# Sheet_STM32_Microcontroller.net
KiCad netlist of a schematic drawn in Altium Designer
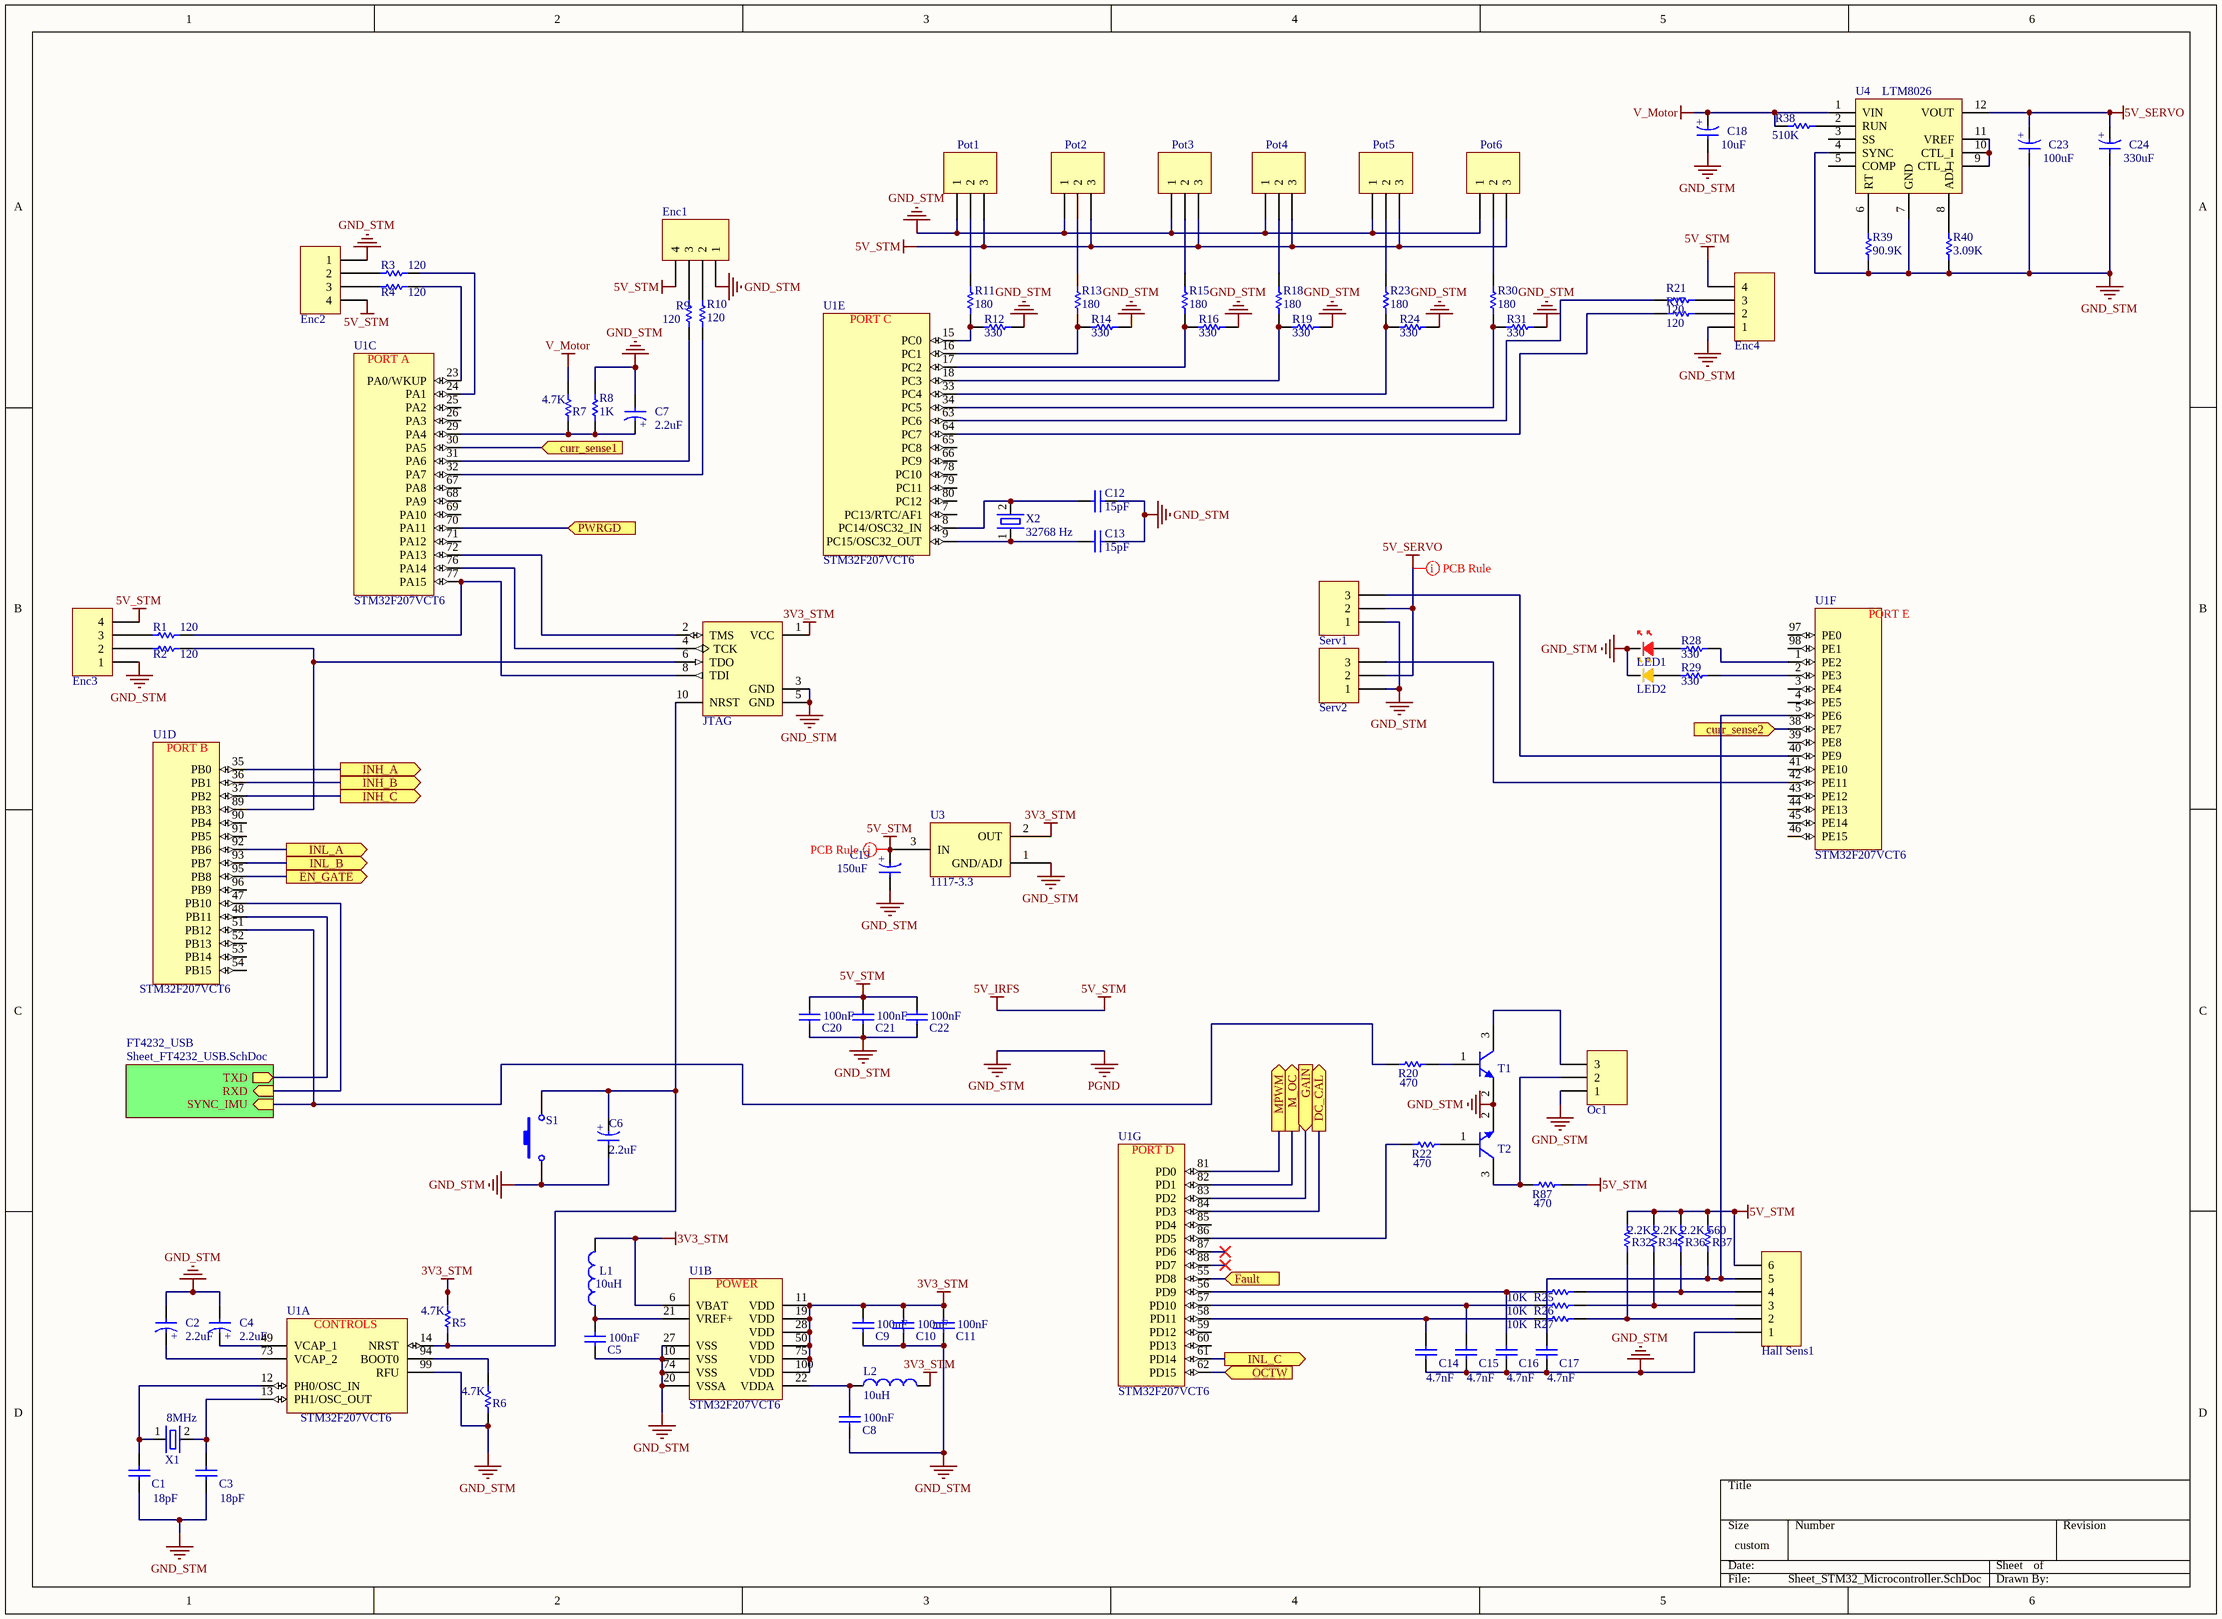
[diagram p0: Sheet_STM32_Microcontroller.SchDoc]

(export (version "E")
  (design (tool "Eeschema 10.0.6"))
  (components
    (comp (ref "C1")
      (value "18pF")
      (footprint "ARPG_PCB_LIB:1608[0603]")
      (description "Capacitor")
      (libsource (lib "AlmaLib1") (part "Cap_BP"))
    )
    (comp (ref "C2")
      (value "2.2uF")
      (footprint "ARPG_PCB_LIB:1608[0603] - Polar")
      (description "Capacitor")
      (libsource (lib "ARPG_PCB_LIB") (part "Cap_E"))
    )
    (comp (ref "C3")
      (value "18pF")
      (footprint "ARPG_PCB_LIB:1608[0603]")
      (description "Capacitor")
      (libsource (lib "AlmaLib1") (part "Cap_BP"))
    )
    (comp (ref "C4")
      (value "2.2uF")
      (footprint "ARPG_PCB_LIB:1608[0603] - Polar")
      (description "Capacitor")
      (libsource (lib "ARPG_PCB_LIB") (part "Cap_E"))
    )
    (comp (ref "C5")
      (value "100nF")
      (footprint "ARPG_PCB_LIB:1608[0603]")
      (description "Capacitor")
      (libsource (lib "AlmaLib1") (part "Cap_BP"))
    )
    (comp (ref "C6")
      (value "2.2uF")
      (footprint "ARPG_PCB_LIB:1608[0603] - Polar")
      (description "Capacitor")
      (libsource (lib "ARPG_PCB_LIB") (part "Cap_E"))
    )
    (comp (ref "C7")
      (value "2.2uF")
      (footprint "ARPG_PCB_LIB:1608[0603] - Polar")
      (description "Capacitor")
      (libsource (lib "ARPG_PCB_LIB") (part "Cap_E"))
    )
    (comp (ref "C8")
      (value "100nF")
      (footprint "ARPG_PCB_LIB:1608[0603]")
      (description "Capacitor")
      (libsource (lib "AlmaLib1") (part "Cap_BP"))
    )
    (comp (ref "C9")
      (value "100nF")
      (footprint "ARPG_PCB_LIB:1608[0603]")
      (description "Capacitor")
      (libsource (lib "AlmaLib1") (part "Cap_BP"))
    )
    (comp (ref "C10")
      (value "100nF")
      (footprint "ARPG_PCB_LIB:1608[0603]")
      (description "Capacitor")
      (libsource (lib "AlmaLib1") (part "Cap_BP"))
    )
    (comp (ref "C11")
      (value "100nF")
      (footprint "ARPG_PCB_LIB:1608[0603]")
      (description "Capacitor")
      (libsource (lib "AlmaLib1") (part "Cap_BP"))
    )
    (comp (ref "C12")
      (value "15pF")
      (footprint "ARPG_PCB_LIB:1608[0603]")
      (description "Capacitor")
      (libsource (lib "AlmaLib1") (part "Cap_BP"))
    )
    (comp (ref "C13")
      (value "15pF")
      (footprint "ARPG_PCB_LIB:1608[0603]")
      (description "Capacitor")
      (libsource (lib "AlmaLib1") (part "Cap_BP"))
    )
    (comp (ref "C14")
      (value "4.7nF")
      (footprint "ARPG_PCB_LIB:1608[0603]")
      (description "Capacitor")
      (libsource (lib "AlmaLib1") (part "Cap_BP"))
    )
    (comp (ref "C15")
      (value "4.7nF")
      (footprint "ARPG_PCB_LIB:1608[0603]")
      (description "Capacitor")
      (libsource (lib "AlmaLib1") (part "Cap_BP"))
    )
    (comp (ref "C16")
      (value "4.7nF")
      (footprint "ARPG_PCB_LIB:1608[0603]")
      (description "Capacitor")
      (libsource (lib "AlmaLib1") (part "Cap_BP"))
    )
    (comp (ref "C17")
      (value "4.7nF")
      (footprint "ARPG_PCB_LIB:1608[0603]")
      (description "Capacitor")
      (libsource (lib "AlmaLib1") (part "Cap_BP"))
    )
    (comp (ref "C18")
      (value "10uF")
      (footprint "ARPG_PCB_LIB:6032 [2312]")
      (description "Capacitor")
      (libsource (lib "AlmaLib1") (part "Cap_E"))
    )
    (comp (ref "C19")
      (value "150uF")
      (footprint "ARPG_PCB_LIB:6032 [2312]")
      (description "Capacitor")
      (libsource (lib "AlmaLib1") (part "Cap_E"))
    )
    (comp (ref "C20")
      (value "100nF")
      (footprint "ARPG_PCB_LIB:1608[0603]")
      (description "Capacitor")
      (libsource (lib "AlmaLib1") (part "Cap_BP"))
    )
    (comp (ref "C21")
      (value "100nF")
      (footprint "ARPG_PCB_LIB:1608[0603]")
      (description "Capacitor")
      (libsource (lib "AlmaLib1") (part "Cap_BP"))
    )
    (comp (ref "C22")
      (value "100nF")
      (footprint "ARPG_PCB_LIB:1608[0603]")
      (description "Capacitor")
      (libsource (lib "AlmaLib1") (part "Cap_BP"))
    )
    (comp (ref "C23")
      (value "100uF")
      (footprint "ARPG_PCB_LIB:6032 [2312]")
      (description "Capacitor")
      (libsource (lib "AlmaLib1") (part "Cap_E"))
    )
    (comp (ref "C24")
      (value "330uF")
      (footprint "ARPG_PCB_LIB:6032 [2312]")
      (description "Capacitor")
      (libsource (lib "AlmaLib1") (part "Cap_E"))
    )
    (comp (ref "H1")
      (value "Enc3")
      (footprint "ARPG_PCB_LIB:Header 4  -MolexPicoBlade")
      (libsource (lib "") (part "Header 4_1"))
    )
    (comp (ref "H2")
      (value "Enc2")
      (footprint "ARPG_PCB_LIB:Header 4  -MolexPicoBlade")
      (libsource (lib "AlmaLib1") (part "Header 4"))
    )
    (comp (ref "H3")
      (value "Enc1")
      (footprint "ARPG_PCB_LIB:Header 4  -MolexPicoBlade")
      (libsource (lib "") (part "Header 4_2"))
    )
    (comp (ref "H4")
      (value "JTAG")
      (footprint "ARPG_PCB_LIB:HDR-2*5-0.05_Without_Through_Hole")
      (description "USB JTAG Programmer")
      (libsource (lib "AlmaLib1") (part "JTAG-ARM"))
    )
    (comp (ref "H5")
      (value "Serv1")
      (footprint "HDR1X3")
      (description "Header, 3-Pin")
      (fields (field (name "PUBLISHER") "Altium Limited"))
      (libsource (lib "Miscellaneous Connectors") (part "Header 3"))
    )
    (comp (ref "H7")
      (value "Pot1")
      (footprint "ARPG_PCB_LIB:Header 3  -MolexPicoBlade")
      (libsource (lib "AlmaLib1") (part "Header 3"))
    )
    (comp (ref "H8")
      (value "Pot2")
      (footprint "ARPG_PCB_LIB:Header 3  -MolexPicoBlade")
      (libsource (lib "AlmaLib1") (part "Header 3"))
    )
    (comp (ref "H9")
      (value "Pot3")
      (footprint "ARPG_PCB_LIB:Header 3  -MolexPicoBlade")
      (libsource (lib "AlmaLib1") (part "Header 3"))
    )
    (comp (ref "H10")
      (value "Pot4")
      (footprint "ARPG_PCB_LIB:Header 3  -MolexPicoBlade")
      (libsource (lib "AlmaLib1") (part "Header 3"))
    )
    (comp (ref "H11")
      (value "Enc4")
      (footprint "ARPG_PCB_LIB:Header 4  -MolexPicoBlade")
      (libsource (lib "") (part "Header 4_3"))
    )
    (comp (ref "H12")
      (value "Pot5")
      (footprint "ARPG_PCB_LIB:Header 3  -MolexPicoBlade")
      (libsource (lib "AlmaLib1") (part "Header 3"))
    )
    (comp (ref "H13")
      (value "Serv2")
      (footprint "HDR1X3")
      (description "Header, 3-Pin")
      (fields (field (name "PUBLISHER") "Altium Limited"))
      (libsource (lib "Miscellaneous Connectors") (part "Header 3"))
    )
    (comp (ref "H16")
      (value "Pot6")
      (footprint "ARPG_PCB_LIB:Header 3  -MolexPicoBlade")
      (libsource (lib "AlmaLib1") (part "Header 3"))
    )
    (comp (ref "H17")
      (value "Oc1")
      (footprint "ARPG_PCB_LIB:Header 3  -MolexPicoBlade")
      (libsource (lib "AlmaLib1") (part "Header 3"))
    )
    (comp (ref "H18")
      (value "Hall Sens1")
      (footprint "ARPG_PCB_LIB:Header 6  ZH-SM4")
      (libsource (lib "AlmaLib1") (part "Header 6"))
    )
    (comp (ref "L1")
      (value "10uH")
      (footprint "ARPG_PCB_LIB:0805")
      (description "Inductor")
      (libsource (lib "AlmaLib1") (part "Inductor"))
    )
    (comp (ref "L2")
      (value "10uH")
      (footprint "ARPG_PCB_LIB:0805")
      (description "Inductor")
      (libsource (lib "AlmaLib1") (part "Inductor"))
    )
    (comp (ref "LED1")
      (value "LEDR")
      (footprint "ARPG_PCB_LIB:2012[0805]")
      (description "LED")
      (libsource (lib "AlmaLib1") (part "LED_R"))
    )
    (comp (ref "LED2")
      (value "LEDY")
      (footprint "ARPG_PCB_LIB:2012[0805]")
      (description "LED")
      (libsource (lib "AlmaLib1") (part "LED_Y"))
    )
    (comp (ref "R1")
      (value "120")
      (footprint "ARPG_PCB_LIB:1608[0603]")
      (description "Res")
      (libsource (lib "AlmaLib1") (part "Res"))
    )
    (comp (ref "R2")
      (value "120")
      (footprint "ARPG_PCB_LIB:1608[0603]")
      (description "Res")
      (libsource (lib "AlmaLib1") (part "Res"))
    )
    (comp (ref "R3")
      (value "120")
      (footprint "ARPG_PCB_LIB:1608[0603]")
      (description "Res")
      (libsource (lib "AlmaLib1") (part "Res"))
    )
    (comp (ref "R4")
      (value "120")
      (footprint "ARPG_PCB_LIB:1608[0603]")
      (description "Res")
      (libsource (lib "AlmaLib1") (part "Res"))
    )
    (comp (ref "R5")
      (value "4.7K")
      (footprint "ARPG_PCB_LIB:1608[0603]")
      (description "Res")
      (libsource (lib "AlmaLib1") (part "Res"))
    )
    (comp (ref "R6")
      (value "4.7K")
      (footprint "ARPG_PCB_LIB:1608[0603]")
      (description "Res")
      (libsource (lib "AlmaLib1") (part "Res"))
    )
    (comp (ref "R7")
      (value "4.7K")
      (footprint "ARPG_PCB_LIB:1608[0603]")
      (description "Res")
      (libsource (lib "AlmaLib1") (part "Res"))
    )
    (comp (ref "R8")
      (value "1K")
      (footprint "ARPG_PCB_LIB:1608[0603]")
      (description "Res")
      (libsource (lib "AlmaLib1") (part "Res"))
    )
    (comp (ref "R9")
      (value "120")
      (footprint "ARPG_PCB_LIB:1608[0603]")
      (description "Res")
      (libsource (lib "AlmaLib1") (part "Res"))
    )
    (comp (ref "R10")
      (value "120")
      (footprint "ARPG_PCB_LIB:1608[0603]")
      (description "Res")
      (libsource (lib "AlmaLib1") (part "Res"))
    )
    (comp (ref "R11")
      (value "180")
      (footprint "ARPG_PCB_LIB:1608[0603]")
      (description "Res")
      (libsource (lib "AlmaLib1") (part "Res"))
    )
    (comp (ref "R12")
      (value "330")
      (footprint "ARPG_PCB_LIB:1608[0603]")
      (description "Res")
      (libsource (lib "AlmaLib1") (part "Res"))
    )
    (comp (ref "R13")
      (value "180")
      (footprint "ARPG_PCB_LIB:1608[0603]")
      (description "Res")
      (libsource (lib "AlmaLib1") (part "Res"))
    )
    (comp (ref "R14")
      (value "330")
      (footprint "ARPG_PCB_LIB:1608[0603]")
      (description "Res")
      (libsource (lib "AlmaLib1") (part "Res"))
    )
    (comp (ref "R15")
      (value "180")
      (footprint "ARPG_PCB_LIB:1608[0603]")
      (description "Res")
      (libsource (lib "AlmaLib1") (part "Res"))
    )
    (comp (ref "R16")
      (value "330")
      (footprint "ARPG_PCB_LIB:1608[0603]")
      (description "Res")
      (libsource (lib "AlmaLib1") (part "Res"))
    )
    (comp (ref "R17")
      (value "120")
      (footprint "ARPG_PCB_LIB:1608[0603]")
      (description "Res")
      (libsource (lib "AlmaLib1") (part "Res"))
    )
    (comp (ref "R18")
      (value "180")
      (footprint "ARPG_PCB_LIB:1608[0603]")
      (description "Res")
      (libsource (lib "AlmaLib1") (part "Res"))
    )
    (comp (ref "R19")
      (value "330")
      (footprint "ARPG_PCB_LIB:1608[0603]")
      (description "Res")
      (libsource (lib "AlmaLib1") (part "Res"))
    )
    (comp (ref "R20")
      (value "470")
      (footprint "ARPG_PCB_LIB:1608[0603]")
      (description "Res")
      (libsource (lib "SchLib1") (part "Res"))
    )
    (comp (ref "R21")
      (value "120")
      (footprint "ARPG_PCB_LIB:1608[0603]")
      (description "Res")
      (libsource (lib "AlmaLib1") (part "Res"))
    )
    (comp (ref "R22")
      (value "470")
      (footprint "ARPG_PCB_LIB:1608[0603]")
      (description "Res")
      (libsource (lib "SchLib1") (part "Res"))
    )
    (comp (ref "R23")
      (value "180")
      (footprint "ARPG_PCB_LIB:1608[0603]")
      (description "Res")
      (libsource (lib "AlmaLib1") (part "Res"))
    )
    (comp (ref "R24")
      (value "330")
      (footprint "ARPG_PCB_LIB:1608[0603]")
      (description "Res")
      (libsource (lib "AlmaLib1") (part "Res"))
    )
    (comp (ref "R25")
      (value "10K")
      (footprint "ARPG_PCB_LIB:1608[0603]")
      (description "Res")
      (libsource (lib "AlmaLib1") (part "Res"))
    )
    (comp (ref "R26")
      (value "10K")
      (footprint "ARPG_PCB_LIB:1608[0603]")
      (description "Res")
      (libsource (lib "AlmaLib1") (part "Res"))
    )
    (comp (ref "R27")
      (value "10K")
      (footprint "ARPG_PCB_LIB:1608[0603]")
      (description "Res")
      (libsource (lib "AlmaLib1") (part "Res"))
    )
    (comp (ref "R28")
      (value "330")
      (footprint "ARPG_PCB_LIB:1608[0603]")
      (description "Res")
      (libsource (lib "AlmaLib1") (part "Res"))
    )
    (comp (ref "R29")
      (value "330")
      (footprint "ARPG_PCB_LIB:1608[0603]")
      (description "Res")
      (libsource (lib "AlmaLib1") (part "Res"))
    )
    (comp (ref "R30")
      (value "180")
      (footprint "ARPG_PCB_LIB:1608[0603]")
      (description "Res")
      (libsource (lib "AlmaLib1") (part "Res"))
    )
    (comp (ref "R31")
      (value "330")
      (footprint "ARPG_PCB_LIB:1608[0603]")
      (description "Res")
      (libsource (lib "AlmaLib1") (part "Res"))
    )
    (comp (ref "R32")
      (value "2.2K")
      (footprint "ARPG_PCB_LIB:1608[0603]")
      (description "Res")
      (libsource (lib "AlmaLib1") (part "Res"))
    )
    (comp (ref "R34")
      (value "2.2K")
      (footprint "ARPG_PCB_LIB:1608[0603]")
      (description "Res")
      (libsource (lib "AlmaLib1") (part "Res"))
    )
    (comp (ref "R36")
      (value "2.2K")
      (footprint "ARPG_PCB_LIB:1608[0603]")
      (description "Res")
      (libsource (lib "AlmaLib1") (part "Res"))
    )
    (comp (ref "R37")
      (value "560")
      (footprint "ARPG_PCB_LIB:1608[0603]")
      (description "Res")
      (libsource (lib "AlmaLib1") (part "Res"))
    )
    (comp (ref "R38")
      (value "510K")
      (footprint "ARPG_PCB_LIB:1608[0603]")
      (description "Res")
      (libsource (lib "AlmaLib1") (part "Res"))
    )
    (comp (ref "R39")
      (value "90.9K")
      (footprint "ARPG_PCB_LIB:1608[0603]")
      (description "Res")
      (libsource (lib "AlmaLib1") (part "Res"))
    )
    (comp (ref "R40")
      (value "3.09K")
      (footprint "ARPG_PCB_LIB:1608[0603]")
      (description "Res")
      (libsource (lib "AlmaLib1") (part "Res"))
    )
    (comp (ref "R87")
      (value "470")
      (footprint "ARPG_PCB_LIB:1608[0603]")
      (description "Res")
      (libsource (lib "SchLib1") (part "Res"))
    )
    (comp (ref "S1")
      (value "SW_TACT")
      (footprint "ARPG_PCB_LIB:PTS645SH50SMTR92_LFS")
      (description "Tactile switch")
      (libsource (lib "AlmaLib1") (part "SW_TACT"))
    )
    (comp (ref "T1")
      (value "BC817")
      (footprint "ARPG_PCB_LIB:SOT-23")
      (description "NPN SMD Transistor")
      (libsource (lib "AlmaLib1") (part "BC817"))
    )
    (comp (ref "T2")
      (value "BC817")
      (footprint "ARPG_PCB_LIB:SOT-23")
      (description "NPN SMD Transistor")
      (libsource (lib "AlmaLib1") (part "BC817"))
    )
    (comp (ref "U1")
      (value "STM32F207VCT6")
      (footprint "ARPG_PCB_LIB:LQFP100_M")
      (description "ARM MCU")
      (libsource (lib "AlmaLib1") (part "STM32F207VCT6"))
    )
    (comp (ref "U3")
      (value "1117-3.3")
      (footprint "ARPG_PCB_LIB:SOT-223")
      (description "3.3V Voltage Regulator")
      (libsource (lib "AlmaLib1") (part "1117-3.3V"))
    )
    (comp (ref "U4")
      (value "LTM8026")
      (footprint "ARPG_PCB_LIB:LGA_Package")
      (libsource (lib "AlmaLib1") (part "LTM8026"))
    )
    (comp (ref "X1")
      (value "8MHz")
      (footprint "ARPG_PCB_LIB:ABM7")
      (description "Crystal Oscillator")
      (fields (field (name "PUBLISHER") "Altium Limited"))
      (libsource (lib "AlmaLib1") (part "XTAL"))
    )
    (comp (ref "X2")
      (value "32768 Hz")
      (footprint "ARPG_PCB_LIB:0805")
      (description "Crystal Oscillator")
      (fields (field (name "PUBLISHER") "Altium Limited"))
      (libsource (lib "AlmaLib1") (part "XTAL"))
    )
  )
  (nets
    (net (code "1") (name "/DC_CAL") (class "Default")
      (node (ref "U1") (pin "84") (pinfunction "PD3_84") (pintype "bidirectional"))
    )
    (net (code "2") (name "/EN_GATE") (class "Default")
      (node (ref "U1") (pin "95") (pinfunction "PB8_95") (pintype "bidirectional"))
    )
    (net (code "3") (name "/Fault") (class "Default")
      (node (ref "U1") (pin "55") (pinfunction "PD8_55") (pintype "bidirectional"))
    )
    (net (code "4") (name "/GAIN") (class "Default")
      (node (ref "U1") (pin "83") (pinfunction "PD2_83") (pintype "bidirectional"))
    )
    (net (code "5") (name "/INH_A") (class "Default")
      (node (ref "U1") (pin "35") (pinfunction "PB0_35") (pintype "bidirectional"))
    )
    (net (code "6") (name "/INH_B") (class "Default")
      (node (ref "U1") (pin "36") (pinfunction "PB1_36") (pintype "bidirectional"))
    )
    (net (code "7") (name "/INH_C") (class "Default")
      (node (ref "U1") (pin "37") (pinfunction "PB2_37") (pintype "bidirectional"))
    )
    (net (code "8") (name "/INL_A") (class "Default")
      (node (ref "U1") (pin "92") (pinfunction "PB6_92") (pintype "bidirectional"))
    )
    (net (code "9") (name "/INL_B") (class "Default")
      (node (ref "U1") (pin "93") (pinfunction "PB7_93") (pintype "bidirectional"))
    )
    (net (code "10") (name "/INL_C") (class "Default")
      (node (ref "U1") (pin "61") (pinfunction "PD14_61") (pintype "bidirectional"))
    )
    (net (code "11") (name "/MPWM") (class "Default")
      (node (ref "U1") (pin "81") (pinfunction "PD0_81") (pintype "bidirectional"))
    )
    (net (code "12") (name "/M_OC") (class "Default")
      (node (ref "U1") (pin "82") (pinfunction "PD1_82") (pintype "bidirectional"))
    )
    (net (code "13") (name "/OCTW") (class "Default")
      (node (ref "U1") (pin "62") (pinfunction "PD15_62") (pintype "bidirectional"))
    )
    (net (code "14") (name "/PWRGD") (class "Default")
      (node (ref "U1") (pin "70") (pinfunction "PA11_70") (pintype "bidirectional"))
    )
    (net (code "15") (name "/RXD") (class "Default")
      (node (ref "U1") (pin "47") (pinfunction "PB10_47") (pintype "bidirectional"))
    )
    (net (code "16") (name "/SYNC_IMU") (class "Default")
      (node (ref "R20") (pin "2") (pinfunction "2_2") (pintype "passive"))
      (node (ref "U1") (pin "51") (pinfunction "PB12_51") (pintype "bidirectional"))
    )
    (net (code "17") (name "/TXD") (class "Default")
      (node (ref "U1") (pin "48") (pinfunction "PB11_48") (pintype "bidirectional"))
    )
    (net (code "18") (name "/curr_sense1") (class "Default")
      (node (ref "U1") (pin "30") (pinfunction "PA5_30") (pintype "bidirectional"))
    )
    (net (code "19") (name "/curr_sense2") (class "Default")
      (node (ref "U1") (pin "38") (pinfunction "PE7_38") (pintype "bidirectional"))
    )
    (net (code "20") (name "3V3_STM") (class "Default")
      (node (ref "C10") (pin "2") (pinfunction "2_2") (pintype "passive"))
      (node (ref "C11") (pin "2") (pinfunction "2_2") (pintype "passive"))
      (node (ref "C9") (pin "2") (pinfunction "2_2") (pintype "passive"))
      (node (ref "H4") (pin "1") (pinfunction "VCC_1") (pintype "power_in"))
      (node (ref "L1") (pin "2") (pinfunction "2_2") (pintype "passive"))
      (node (ref "L2") (pin "2") (pinfunction "2_2") (pintype "passive"))
      (node (ref "R5") (pin "2") (pinfunction "2_2") (pintype "passive"))
      (node (ref "U1") (pin "100") (pinfunction "VDD_100") (pintype "power_in"))
      (node (ref "U1") (pin "11") (pinfunction "VDD_11") (pintype "power_in"))
      (node (ref "U1") (pin "19") (pinfunction "VDD_19") (pintype "power_in"))
      (node (ref "U1") (pin "28") (pinfunction "VDD_28") (pintype "power_in"))
      (node (ref "U1") (pin "50") (pinfunction "VDD_50") (pintype "power_in"))
      (node (ref "U1") (pin "6") (pinfunction "VBAT_6") (pintype "power_in"))
      (node (ref "U1") (pin "75") (pinfunction "VDD_75") (pintype "power_in"))
      (node (ref "U3") (pin "2") (pinfunction "OUT_2") (pintype "passive"))
    )
    (net (code "21") (name "5V_IRFS") (class "Default")
      (node (ref "C19") (pin "2") (pinfunction "2_2") (pintype "passive"))
      (node (ref "C20") (pin "2") (pinfunction "2_2") (pintype "passive"))
      (node (ref "C21") (pin "2") (pinfunction "2_2") (pintype "passive"))
      (node (ref "C22") (pin "2") (pinfunction "2_2") (pintype "passive"))
      (node (ref "H1") (pin "4") (pinfunction "4_4") (pintype "passive"))
      (node (ref "H10") (pin "3") (pinfunction "3_3") (pintype "passive"))
      (node (ref "H11") (pin "4") (pinfunction "4_4") (pintype "passive"))
      (node (ref "H12") (pin "3") (pinfunction "3_3") (pintype "passive"))
      (node (ref "H16") (pin "3") (pinfunction "3_3") (pintype "passive"))
      (node (ref "H18") (pin "6") (pinfunction "6_6") (pintype "passive"))
      (node (ref "H2") (pin "4") (pinfunction "4_4") (pintype "passive"))
      (node (ref "H3") (pin "4") (pinfunction "4_4") (pintype "passive"))
      (node (ref "H7") (pin "3") (pinfunction "3_3") (pintype "passive"))
      (node (ref "H8") (pin "3") (pinfunction "3_3") (pintype "passive"))
      (node (ref "H9") (pin "3") (pinfunction "3_3") (pintype "passive"))
      (node (ref "R32") (pin "2") (pinfunction "2_2") (pintype "passive"))
      (node (ref "R34") (pin "2") (pinfunction "2_2") (pintype "passive"))
      (node (ref "R36") (pin "2") (pinfunction "2_2") (pintype "passive"))
      (node (ref "R37") (pin "2") (pinfunction "2_2") (pintype "passive"))
      (node (ref "R87") (pin "1") (pinfunction "1_1") (pintype "passive"))
      (node (ref "U3") (pin "3") (pinfunction "IN_3") (pintype "passive"))
    )
    (net (code "22") (name "5V_SERVO") (class "Default")
      (node (ref "C23") (pin "2") (pinfunction "2_2") (pintype "passive"))
      (node (ref "C24") (pin "2") (pinfunction "2_2") (pintype "passive"))
      (node (ref "H13") (pin "2") (pinfunction "2_2") (pintype "passive"))
      (node (ref "H5") (pin "2") (pinfunction "2_2") (pintype "passive"))
      (node (ref "U4") (pin "12") (pinfunction "VOUT_12") (pintype "power_in"))
    )
    (net (code "23") (name "GND_STM") (class "Default")
      (node (ref "C1") (pin "1") (pinfunction "1_1") (pintype "passive"))
      (node (ref "C10") (pin "1") (pinfunction "1_1") (pintype "passive"))
      (node (ref "C11") (pin "1") (pinfunction "1_1") (pintype "passive"))
      (node (ref "C12") (pin "2") (pinfunction "2_2") (pintype "passive"))
      (node (ref "C13") (pin "2") (pinfunction "2_2") (pintype "passive"))
      (node (ref "C14") (pin "1") (pinfunction "1_1") (pintype "passive"))
      (node (ref "C15") (pin "1") (pinfunction "1_1") (pintype "passive"))
      (node (ref "C16") (pin "1") (pinfunction "1_1") (pintype "passive"))
      (node (ref "C17") (pin "1") (pinfunction "1_1") (pintype "passive"))
      (node (ref "C18") (pin "1") (pinfunction "1_1") (pintype "passive"))
      (node (ref "C19") (pin "1") (pinfunction "1_1") (pintype "passive"))
      (node (ref "C2") (pin "1") (pinfunction "1_1") (pintype "passive"))
      (node (ref "C20") (pin "1") (pinfunction "1_1") (pintype "passive"))
      (node (ref "C21") (pin "1") (pinfunction "1_1") (pintype "passive"))
      (node (ref "C22") (pin "1") (pinfunction "1_1") (pintype "passive"))
      (node (ref "C23") (pin "1") (pinfunction "1_1") (pintype "passive"))
      (node (ref "C24") (pin "1") (pinfunction "1_1") (pintype "passive"))
      (node (ref "C3") (pin "1") (pinfunction "1_1") (pintype "passive"))
      (node (ref "C4") (pin "1") (pinfunction "1_1") (pintype "passive"))
      (node (ref "C5") (pin "1") (pinfunction "1_1") (pintype "passive"))
      (node (ref "C6") (pin "1") (pinfunction "1_1") (pintype "passive"))
      (node (ref "C7") (pin "1") (pinfunction "1_1") (pintype "passive"))
      (node (ref "C8") (pin "1") (pinfunction "1_1") (pintype "passive"))
      (node (ref "C9") (pin "1") (pinfunction "1_1") (pintype "passive"))
      (node (ref "H1") (pin "1") (pinfunction "1_1") (pintype "passive"))
      (node (ref "H10") (pin "1") (pinfunction "1_1") (pintype "passive"))
      (node (ref "H11") (pin "1") (pinfunction "1_1") (pintype "passive"))
      (node (ref "H12") (pin "1") (pinfunction "1_1") (pintype "passive"))
      (node (ref "H13") (pin "1") (pinfunction "1_1") (pintype "passive"))
      (node (ref "H16") (pin "1") (pinfunction "1_1") (pintype "passive"))
      (node (ref "H17") (pin "1") (pinfunction "1_1") (pintype "passive"))
      (node (ref "H18") (pin "1") (pinfunction "1_1") (pintype "passive"))
      (node (ref "H2") (pin "1") (pinfunction "1_1") (pintype "passive"))
      (node (ref "H3") (pin "1") (pinfunction "1_1") (pintype "passive"))
      (node (ref "H4") (pin "3") (pinfunction "GND_3") (pintype "power_in"))
      (node (ref "H4") (pin "5") (pinfunction "GND_5") (pintype "power_in"))
      (node (ref "H5") (pin "1") (pinfunction "1_1") (pintype "passive"))
      (node (ref "H7") (pin "1") (pinfunction "1_1") (pintype "passive"))
      (node (ref "H8") (pin "1") (pinfunction "1_1") (pintype "passive"))
      (node (ref "H9") (pin "1") (pinfunction "1_1") (pintype "passive"))
      (node (ref "LED1") (pin "2") (pinfunction "K_2") (pintype "passive"))
      (node (ref "LED2") (pin "2") (pinfunction "K_2") (pintype "passive"))
      (node (ref "R12") (pin "2") (pinfunction "2_2") (pintype "passive"))
      (node (ref "R14") (pin "2") (pinfunction "2_2") (pintype "passive"))
      (node (ref "R16") (pin "2") (pinfunction "2_2") (pintype "passive"))
      (node (ref "R19") (pin "2") (pinfunction "2_2") (pintype "passive"))
      (node (ref "R24") (pin "2") (pinfunction "2_2") (pintype "passive"))
      (node (ref "R31") (pin "2") (pinfunction "2_2") (pintype "passive"))
      (node (ref "R39") (pin "1") (pinfunction "1_1") (pintype "passive"))
      (node (ref "R40") (pin "1") (pinfunction "1_1") (pintype "passive"))
      (node (ref "R6") (pin "1") (pinfunction "1_1") (pintype "passive"))
      (node (ref "R8") (pin "2") (pinfunction "2_2") (pintype "passive"))
      (node (ref "S1") (pin "1") (pinfunction "1_1") (pintype "passive"))
      (node (ref "T1") (pin "2") (pinfunction "E_2") (pintype "passive"))
      (node (ref "T2") (pin "2") (pinfunction "E_2") (pintype "passive"))
      (node (ref "U1") (pin "10") (pinfunction "VSS_10") (pintype "power_in"))
      (node (ref "U1") (pin "20") (pinfunction "VSSA_20") (pintype "power_in"))
      (node (ref "U1") (pin "27") (pinfunction "VSS_27") (pintype "power_in"))
      (node (ref "U1") (pin "74") (pinfunction "VSS_74") (pintype "power_in"))
      (node (ref "U1") (pin "99") (pinfunction "RFU_99") (pintype "passive"))
      (node (ref "U3") (pin "1") (pinfunction "GND/ADJ_1") (pintype "passive"))
      (node (ref "U4") (pin "4") (pinfunction "SYNC_4") (pintype "power_in"))
      (node (ref "U4") (pin "7") (pinfunction "GND_7") (pintype "power_in"))
    )
    (net (code "24") (name "Net-(H1-Pad2)") (class "Default")
      (node (ref "H1") (pin "2") (pinfunction "2_2") (pintype "passive"))
      (node (ref "R2") (pin "1") (pinfunction "1_1") (pintype "passive"))
    )
    (net (code "25") (name "Net-(H1-Pad3)") (class "Default")
      (node (ref "H1") (pin "3") (pinfunction "3_3") (pintype "passive"))
      (node (ref "R1") (pin "1") (pinfunction "1_1") (pintype "passive"))
    )
    (net (code "26") (name "Net-(H2-Pad2)") (class "Default")
      (node (ref "H2") (pin "2") (pinfunction "2_2") (pintype "passive"))
      (node (ref "R3") (pin "1") (pinfunction "1_1") (pintype "passive"))
    )
    (net (code "27") (name "Net-(H2-Pad3)") (class "Default")
      (node (ref "H2") (pin "3") (pinfunction "3_3") (pintype "passive"))
      (node (ref "R4") (pin "1") (pinfunction "1_1") (pintype "passive"))
    )
    (net (code "28") (name "Net-(H3-Pad2)") (class "Default")
      (node (ref "H3") (pin "2") (pinfunction "2_2") (pintype "passive"))
      (node (ref "R10") (pin "1") (pinfunction "1_1") (pintype "passive"))
    )
    (net (code "29") (name "Net-(H3-Pad3)") (class "Default")
      (node (ref "H3") (pin "3") (pinfunction "3_3") (pintype "passive"))
      (node (ref "R9") (pin "1") (pinfunction "1_1") (pintype "passive"))
    )
    (net (code "30") (name "Net-(H4-NRST)") (class "Default")
      (node (ref "C6") (pin "2") (pinfunction "2_2") (pintype "passive"))
      (node (ref "H4") (pin "10") (pinfunction "NRST_10") (pintype "passive"))
      (node (ref "R5") (pin "1") (pinfunction "1_1") (pintype "passive"))
      (node (ref "S1") (pin "2") (pinfunction "2_2") (pintype "passive"))
      (node (ref "U1") (pin "14") (pinfunction "NRST_14") (pintype "bidirectional"))
    )
    (net (code "31") (name "Net-(H4-TCK)") (class "Default")
      (node (ref "H4") (pin "4") (pinfunction "TCK_4") (pintype "output"))
      (node (ref "U1") (pin "76") (pinfunction "PA14_76") (pintype "bidirectional"))
    )
    (net (code "32") (name "Net-(H4-TDI)") (class "Default")
      (node (ref "H4") (pin "8") (pinfunction "TDI_8") (pintype "output"))
      (node (ref "R1") (pin "2") (pinfunction "2_2") (pintype "passive"))
      (node (ref "U1") (pin "77") (pinfunction "PA15_77") (pintype "bidirectional"))
    )
    (net (code "33") (name "Net-(H4-TDO)") (class "Default")
      (node (ref "H4") (pin "6") (pinfunction "TDO_6") (pintype "input"))
      (node (ref "R2") (pin "2") (pinfunction "2_2") (pintype "passive"))
      (node (ref "U1") (pin "89") (pinfunction "PB3_89") (pintype "bidirectional"))
    )
    (net (code "34") (name "Net-(H4-TMS)") (class "Default")
      (node (ref "H4") (pin "2") (pinfunction "TMS_2") (pintype "bidirectional"))
      (node (ref "U1") (pin "72") (pinfunction "PA13_72") (pintype "bidirectional"))
    )
    (net (code "35") (name "Net-(H7-Pad2)") (class "Default")
      (node (ref "H7") (pin "2") (pinfunction "2_2") (pintype "passive"))
      (node (ref "R11") (pin "2") (pinfunction "2_2") (pintype "passive"))
    )
    (net (code "36") (name "Net-(H8-Pad2)") (class "Default")
      (node (ref "H8") (pin "2") (pinfunction "2_2") (pintype "passive"))
      (node (ref "R13") (pin "2") (pinfunction "2_2") (pintype "passive"))
    )
    (net (code "37") (name "Net-(H9-Pad2)") (class "Default")
      (node (ref "H9") (pin "2") (pinfunction "2_2") (pintype "passive"))
      (node (ref "R15") (pin "2") (pinfunction "2_2") (pintype "passive"))
    )
    (net (code "38") (name "Net-(H10-Pad2)") (class "Default")
      (node (ref "H10") (pin "2") (pinfunction "2_2") (pintype "passive"))
      (node (ref "R18") (pin "2") (pinfunction "2_2") (pintype "passive"))
    )
    (net (code "39") (name "Net-(H11-Pad2)") (class "Default")
      (node (ref "H11") (pin "2") (pinfunction "2_2") (pintype "passive"))
      (node (ref "R17") (pin "1") (pinfunction "1_1") (pintype "passive"))
    )
    (net (code "40") (name "Net-(H11-Pad3)") (class "Default")
      (node (ref "H11") (pin "3") (pinfunction "3_3") (pintype "passive"))
      (node (ref "R21") (pin "1") (pinfunction "1_1") (pintype "passive"))
    )
    (net (code "41") (name "Net-(H12-Pad2)") (class "Default")
      (node (ref "H12") (pin "2") (pinfunction "2_2") (pintype "passive"))
      (node (ref "R23") (pin "2") (pinfunction "2_2") (pintype "passive"))
    )
    (net (code "42") (name "Net-(H16-Pad2)") (class "Default")
      (node (ref "H16") (pin "2") (pinfunction "2_2") (pintype "passive"))
      (node (ref "R30") (pin "2") (pinfunction "2_2") (pintype "passive"))
    )
    (net (code "43") (name "Net-(H18-Pad2)") (class "Default")
      (node (ref "H18") (pin "2") (pinfunction "2_2") (pintype "passive"))
      (node (ref "R27") (pin "2") (pinfunction "2_2") (pintype "passive"))
      (node (ref "R32") (pin "1") (pinfunction "1_1") (pintype "passive"))
    )
    (net (code "44") (name "Net-(H18-Pad3)") (class "Default")
      (node (ref "H18") (pin "3") (pinfunction "3_3") (pintype "passive"))
      (node (ref "R26") (pin "2") (pinfunction "2_2") (pintype "passive"))
      (node (ref "R34") (pin "1") (pinfunction "1_1") (pintype "passive"))
    )
    (net (code "45") (name "Net-(H18-Pad4)") (class "Default")
      (node (ref "H18") (pin "4") (pinfunction "4_4") (pintype "passive"))
      (node (ref "R25") (pin "2") (pinfunction "2_2") (pintype "passive"))
      (node (ref "R36") (pin "1") (pinfunction "1_1") (pintype "passive"))
    )
    (net (code "46") (name "Net-(LED1-A)") (class "Default")
      (node (ref "LED1") (pin "1") (pinfunction "A_1") (pintype "passive"))
      (node (ref "R28") (pin "1") (pinfunction "1_1") (pintype "passive"))
    )
    (net (code "47") (name "Net-(LED2-A)") (class "Default")
      (node (ref "LED2") (pin "1") (pinfunction "A_1") (pintype "passive"))
      (node (ref "R29") (pin "1") (pinfunction "1_1") (pintype "passive"))
    )
    (net (code "48") (name "Net-(T1-B)") (class "Default")
      (node (ref "R20") (pin "1") (pinfunction "1_1") (pintype "passive"))
      (node (ref "T1") (pin "1") (pinfunction "B_1") (pintype "passive"))
    )
    (net (code "49") (name "Net-(T1-C)") (class "Default")
      (node (ref "H17") (pin "3") (pinfunction "3_3") (pintype "passive"))
      (node (ref "T1") (pin "3") (pinfunction "C_3") (pintype "passive"))
    )
    (net (code "50") (name "Net-(T2-B)") (class "Default")
      (node (ref "R22") (pin "1") (pinfunction "1_1") (pintype "passive"))
      (node (ref "T2") (pin "1") (pinfunction "B_1") (pintype "passive"))
    )
    (net (code "51") (name "Net-(T2-C)") (class "Default")
      (node (ref "H17") (pin "2") (pinfunction "2_2") (pintype "passive"))
      (node (ref "R87") (pin "2") (pinfunction "2_2") (pintype "passive"))
      (node (ref "T2") (pin "3") (pinfunction "C_3") (pintype "passive"))
    )
    (net (code "52") (name "Net-(U1A-BOOT0)") (class "Default")
      (node (ref "R6") (pin "2") (pinfunction "2_2") (pintype "passive"))
      (node (ref "U1") (pin "94") (pinfunction "BOOT0_94") (pintype "passive"))
    )
    (net (code "53") (name "Net-(U1A-PH0{slash}OSC_IN)") (class "Default")
      (node (ref "C1") (pin "2") (pinfunction "2_2") (pintype "passive"))
      (node (ref "U1") (pin "12") (pinfunction "PH0/OSC_IN_12") (pintype "bidirectional"))
      (node (ref "X1") (pin "1") (pinfunction "OSC1_1") (pintype "passive"))
    )
    (net (code "54") (name "Net-(U1A-PH1{slash}OSC_OUT)") (class "Default")
      (node (ref "C3") (pin "2") (pinfunction "2_2") (pintype "passive"))
      (node (ref "U1") (pin "13") (pinfunction "PH1/OSC_OUT_13") (pintype "bidirectional"))
      (node (ref "X1") (pin "2") (pinfunction "OSC2_2") (pintype "passive"))
    )
    (net (code "55") (name "Net-(U1A-VCAP_1)") (class "Default")
      (node (ref "C4") (pin "2") (pinfunction "2_2") (pintype "passive"))
      (node (ref "U1") (pin "49") (pinfunction "VCAP_1_49") (pintype "passive"))
    )
    (net (code "56") (name "Net-(U1A-VCAP_2)") (class "Default")
      (node (ref "C2") (pin "2") (pinfunction "2_2") (pintype "passive"))
      (node (ref "U1") (pin "73") (pinfunction "VCAP_2_73") (pintype "passive"))
    )
    (net (code "57") (name "Net-(U1B-VDDA)") (class "Default")
      (node (ref "C8") (pin "2") (pinfunction "2_2") (pintype "passive"))
      (node (ref "L2") (pin "1") (pinfunction "1_1") (pintype "passive"))
      (node (ref "U1") (pin "22") (pinfunction "VDDA_22") (pintype "power_in"))
    )
    (net (code "58") (name "Net-(U1B-VREF+)") (class "Default")
      (node (ref "C5") (pin "2") (pinfunction "2_2") (pintype "passive"))
      (node (ref "L1") (pin "1") (pinfunction "1_1") (pintype "passive"))
      (node (ref "U1") (pin "21") (pinfunction "VREF+_21") (pintype "passive"))
    )
    (net (code "59") (name "Net-(U1C-PA0{slash}WKUP)") (class "Default")
      (node (ref "R4") (pin "2") (pinfunction "2_2") (pintype "passive"))
      (node (ref "U1") (pin "23") (pinfunction "PA0/WKUP_23") (pintype "bidirectional"))
    )
    (net (code "60") (name "Net-(U1C-PA1)") (class "Default")
      (node (ref "R3") (pin "2") (pinfunction "2_2") (pintype "passive"))
      (node (ref "U1") (pin "24") (pinfunction "PA1_24") (pintype "bidirectional"))
    )
    (net (code "61") (name "Net-(U1C-PA4)") (class "Default")
      (node (ref "C7") (pin "2") (pinfunction "2_2") (pintype "passive"))
      (node (ref "R7") (pin "1") (pinfunction "1_1") (pintype "passive"))
      (node (ref "R8") (pin "1") (pinfunction "1_1") (pintype "passive"))
      (node (ref "U1") (pin "29") (pinfunction "PA4_29") (pintype "bidirectional"))
    )
    (net (code "62") (name "Net-(U1C-PA6)") (class "Default")
      (node (ref "R9") (pin "2") (pinfunction "2_2") (pintype "passive"))
      (node (ref "U1") (pin "31") (pinfunction "PA6_31") (pintype "bidirectional"))
    )
    (net (code "63") (name "Net-(U1C-PA7)") (class "Default")
      (node (ref "R10") (pin "2") (pinfunction "2_2") (pintype "passive"))
      (node (ref "U1") (pin "32") (pinfunction "PA7_32") (pintype "bidirectional"))
    )
    (net (code "64") (name "Net-(U1E-PC0)") (class "Default")
      (node (ref "R11") (pin "1") (pinfunction "1_1") (pintype "passive"))
      (node (ref "R12") (pin "1") (pinfunction "1_1") (pintype "passive"))
      (node (ref "U1") (pin "15") (pinfunction "PC0_15") (pintype "bidirectional"))
    )
    (net (code "65") (name "Net-(U1E-PC1)") (class "Default")
      (node (ref "R13") (pin "1") (pinfunction "1_1") (pintype "passive"))
      (node (ref "R14") (pin "1") (pinfunction "1_1") (pintype "passive"))
      (node (ref "U1") (pin "16") (pinfunction "PC1_16") (pintype "bidirectional"))
    )
    (net (code "66") (name "Net-(U1E-PC2)") (class "Default")
      (node (ref "R15") (pin "1") (pinfunction "1_1") (pintype "passive"))
      (node (ref "R16") (pin "1") (pinfunction "1_1") (pintype "passive"))
      (node (ref "U1") (pin "17") (pinfunction "PC2_17") (pintype "bidirectional"))
    )
    (net (code "67") (name "Net-(U1E-PC3)") (class "Default")
      (node (ref "R18") (pin "1") (pinfunction "1_1") (pintype "passive"))
      (node (ref "R19") (pin "1") (pinfunction "1_1") (pintype "passive"))
      (node (ref "U1") (pin "18") (pinfunction "PC3_18") (pintype "bidirectional"))
    )
    (net (code "68") (name "Net-(U1E-PC4)") (class "Default")
      (node (ref "R23") (pin "1") (pinfunction "1_1") (pintype "passive"))
      (node (ref "R24") (pin "1") (pinfunction "1_1") (pintype "passive"))
      (node (ref "U1") (pin "33") (pinfunction "PC4_33") (pintype "bidirectional"))
    )
    (net (code "69") (name "Net-(U1E-PC5)") (class "Default")
      (node (ref "R30") (pin "1") (pinfunction "1_1") (pintype "passive"))
      (node (ref "R31") (pin "1") (pinfunction "1_1") (pintype "passive"))
      (node (ref "U1") (pin "34") (pinfunction "PC5_34") (pintype "bidirectional"))
    )
    (net (code "70") (name "Net-(U1E-PC6)") (class "Default")
      (node (ref "R21") (pin "2") (pinfunction "2_2") (pintype "passive"))
      (node (ref "U1") (pin "63") (pinfunction "PC6_63") (pintype "bidirectional"))
    )
    (net (code "71") (name "Net-(U1E-PC7)") (class "Default")
      (node (ref "R17") (pin "2") (pinfunction "2_2") (pintype "passive"))
      (node (ref "U1") (pin "64") (pinfunction "PC7_64") (pintype "bidirectional"))
    )
    (net (code "72") (name "Net-(U1E-PC14{slash}OSC32_IN)") (class "Default")
      (node (ref "C12") (pin "1") (pinfunction "1_1") (pintype "passive"))
      (node (ref "U1") (pin "8") (pinfunction "PC14/OSC32_IN_8") (pintype "bidirectional"))
      (node (ref "X2") (pin "2") (pinfunction "OSC2_2") (pintype "passive"))
    )
    (net (code "73") (name "Net-(U1E-PC15{slash}OSC32_OUT)") (class "Default")
      (node (ref "C13") (pin "1") (pinfunction "1_1") (pintype "passive"))
      (node (ref "U1") (pin "9") (pinfunction "PC15/OSC32_OUT_9") (pintype "bidirectional"))
      (node (ref "X2") (pin "1") (pinfunction "OSC1_1") (pintype "passive"))
    )
    (net (code "74") (name "Net-(U1F-PE2)") (class "Default")
      (node (ref "R28") (pin "2") (pinfunction "2_2") (pintype "passive"))
      (node (ref "U1") (pin "1") (pinfunction "PE2_1") (pintype "bidirectional"))
    )
    (net (code "75") (name "Net-(U1F-PE3)") (class "Default")
      (node (ref "R29") (pin "2") (pinfunction "2_2") (pintype "passive"))
      (node (ref "U1") (pin "2") (pinfunction "PE3_2") (pintype "bidirectional"))
    )
    (net (code "76") (name "Net-(U1F-PE6)") (class "Default")
      (node (ref "C17") (pin "2") (pinfunction "2_2") (pintype "passive"))
      (node (ref "H18") (pin "5") (pinfunction "5_5") (pintype "passive"))
      (node (ref "R37") (pin "1") (pinfunction "1_1") (pintype "passive"))
      (node (ref "U1") (pin "5") (pinfunction "PE6_5") (pintype "bidirectional"))
    )
    (net (code "77") (name "Net-(U1F-PE9)") (class "Default")
      (node (ref "H5") (pin "3") (pinfunction "3_3") (pintype "passive"))
      (node (ref "U1") (pin "40") (pinfunction "PE9_40") (pintype "bidirectional"))
    )
    (net (code "78") (name "Net-(U1F-PE11)") (class "Default")
      (node (ref "H13") (pin "3") (pinfunction "3_3") (pintype "passive"))
      (node (ref "U1") (pin "42") (pinfunction "PE11_42") (pintype "bidirectional"))
    )
    (net (code "79") (name "Net-(U1G-PD5)") (class "Default")
      (node (ref "R22") (pin "2") (pinfunction "2_2") (pintype "passive"))
      (node (ref "U1") (pin "86") (pinfunction "PD5_86") (pintype "bidirectional"))
    )
    (net (code "80") (name "Net-(U1G-PD9)") (class "Default")
      (node (ref "C16") (pin "2") (pinfunction "2_2") (pintype "passive"))
      (node (ref "R25") (pin "1") (pinfunction "1_1") (pintype "passive"))
      (node (ref "U1") (pin "56") (pinfunction "PD9_56") (pintype "bidirectional"))
    )
    (net (code "81") (name "Net-(U1G-PD10)") (class "Default")
      (node (ref "C15") (pin "2") (pinfunction "2_2") (pintype "passive"))
      (node (ref "R26") (pin "1") (pinfunction "1_1") (pintype "passive"))
      (node (ref "U1") (pin "57") (pinfunction "PD10_57") (pintype "bidirectional"))
    )
    (net (code "82") (name "Net-(U1G-PD11)") (class "Default")
      (node (ref "C14") (pin "2") (pinfunction "2_2") (pintype "passive"))
      (node (ref "R27") (pin "1") (pinfunction "1_1") (pintype "passive"))
      (node (ref "U1") (pin "58") (pinfunction "PD11_58") (pintype "bidirectional"))
    )
    (net (code "83") (name "Net-(U4-ADJ)") (class "Default")
      (node (ref "R40") (pin "2") (pinfunction "2_2") (pintype "passive"))
      (node (ref "U4") (pin "8") (pinfunction "ADJ_8") (pintype "power_in"))
    )
    (net (code "84") (name "Net-(U4-CTL_I)") (class "Default")
      (node (ref "U4") (pin "10") (pinfunction "CTL_I_10") (pintype "power_in"))
      (node (ref "U4") (pin "11") (pinfunction "VREF_11") (pintype "power_in"))
      (node (ref "U4") (pin "9") (pinfunction "CTL_T_9") (pintype "power_in"))
    )
    (net (code "85") (name "Net-(U4-RT)") (class "Default")
      (node (ref "R39") (pin "2") (pinfunction "2_2") (pintype "passive"))
      (node (ref "U4") (pin "6") (pinfunction "RT_6") (pintype "power_in"))
    )
    (net (code "86") (name "Net-(U4-RUN)") (class "Default")
      (node (ref "R38") (pin "2") (pinfunction "2_2") (pintype "passive"))
      (node (ref "U4") (pin "2") (pinfunction "RUN_2") (pintype "power_in"))
    )
    (net (code "87") (name "V_Motor") (class "Default")
      (node (ref "C18") (pin "2") (pinfunction "2_2") (pintype "passive"))
      (node (ref "R38") (pin "1") (pinfunction "1_1") (pintype "passive"))
      (node (ref "R7") (pin "2") (pinfunction "2_2") (pintype "passive"))
      (node (ref "U4") (pin "1") (pinfunction "VIN_1") (pintype "power_in"))
    )
    (net (code "88") (name "unconnected-(U1C-PA2-Pad25)") (class "Default")
      (node (ref "U1") (pin "25") (pinfunction "PA2_25") (pintype "bidirectional"))
    )
    (net (code "89") (name "unconnected-(U1C-PA3-Pad26)") (class "Default")
      (node (ref "U1") (pin "26") (pinfunction "PA3_26") (pintype "bidirectional"))
    )
    (net (code "90") (name "unconnected-(U1C-PA8-Pad67)") (class "Default")
      (node (ref "U1") (pin "67") (pinfunction "PA8_67") (pintype "bidirectional"))
    )
    (net (code "91") (name "unconnected-(U1C-PA9-Pad68)") (class "Default")
      (node (ref "U1") (pin "68") (pinfunction "PA9_68") (pintype "bidirectional"))
    )
    (net (code "92") (name "unconnected-(U1C-PA10-Pad69)") (class "Default")
      (node (ref "U1") (pin "69") (pinfunction "PA10_69") (pintype "bidirectional"))
    )
    (net (code "93") (name "unconnected-(U1C-PA12-Pad71)") (class "Default")
      (node (ref "U1") (pin "71") (pinfunction "PA12_71") (pintype "bidirectional"))
    )
    (net (code "94") (name "unconnected-(U1D-PB4-Pad90)") (class "Default")
      (node (ref "U1") (pin "90") (pinfunction "PB4_90") (pintype "bidirectional"))
    )
    (net (code "95") (name "unconnected-(U1D-PB5-Pad91)") (class "Default")
      (node (ref "U1") (pin "91") (pinfunction "PB5_91") (pintype "bidirectional"))
    )
    (net (code "96") (name "unconnected-(U1D-PB9-Pad96)") (class "Default")
      (node (ref "U1") (pin "96") (pinfunction "PB9_96") (pintype "bidirectional"))
    )
    (net (code "97") (name "unconnected-(U1D-PB13-Pad52)") (class "Default")
      (node (ref "U1") (pin "52") (pinfunction "PB13_52") (pintype "bidirectional"))
    )
    (net (code "98") (name "unconnected-(U1D-PB14-Pad53)") (class "Default")
      (node (ref "U1") (pin "53") (pinfunction "PB14_53") (pintype "bidirectional"))
    )
    (net (code "99") (name "unconnected-(U1D-PB15-Pad54)") (class "Default")
      (node (ref "U1") (pin "54") (pinfunction "PB15_54") (pintype "bidirectional"))
    )
    (net (code "100") (name "unconnected-(U1E-PC8-Pad65)") (class "Default")
      (node (ref "U1") (pin "65") (pinfunction "PC8_65") (pintype "bidirectional"))
    )
    (net (code "101") (name "unconnected-(U1E-PC9-Pad66)") (class "Default")
      (node (ref "U1") (pin "66") (pinfunction "PC9_66") (pintype "bidirectional"))
    )
    (net (code "102") (name "unconnected-(U1E-PC10-Pad78)") (class "Default")
      (node (ref "U1") (pin "78") (pinfunction "PC10_78") (pintype "bidirectional"))
    )
    (net (code "103") (name "unconnected-(U1E-PC11-Pad79)") (class "Default")
      (node (ref "U1") (pin "79") (pinfunction "PC11_79") (pintype "bidirectional"))
    )
    (net (code "104") (name "unconnected-(U1E-PC12-Pad80)") (class "Default")
      (node (ref "U1") (pin "80") (pinfunction "PC12_80") (pintype "bidirectional"))
    )
    (net (code "105") (name "unconnected-(U1E-PC13{slash}RTC{slash}AF1-Pad7)") (class "Default")
      (node (ref "U1") (pin "7") (pinfunction "PC13/RTC/AF1_7") (pintype "bidirectional"))
    )
    (net (code "106") (name "unconnected-(U1F-PE0-Pad97)") (class "Default")
      (node (ref "U1") (pin "97") (pinfunction "PE0_97") (pintype "bidirectional"))
    )
    (net (code "107") (name "unconnected-(U1F-PE1-Pad98)") (class "Default")
      (node (ref "U1") (pin "98") (pinfunction "PE1_98") (pintype "bidirectional"))
    )
    (net (code "108") (name "unconnected-(U1F-PE4-Pad3)") (class "Default")
      (node (ref "U1") (pin "3") (pinfunction "PE4_3") (pintype "bidirectional"))
    )
    (net (code "109") (name "unconnected-(U1F-PE5-Pad4)") (class "Default")
      (node (ref "U1") (pin "4") (pinfunction "PE5_4") (pintype "bidirectional"))
    )
    (net (code "110") (name "unconnected-(U1F-PE8-Pad39)") (class "Default")
      (node (ref "U1") (pin "39") (pinfunction "PE8_39") (pintype "bidirectional"))
    )
    (net (code "111") (name "unconnected-(U1F-PE10-Pad41)") (class "Default")
      (node (ref "U1") (pin "41") (pinfunction "PE10_41") (pintype "bidirectional"))
    )
    (net (code "112") (name "unconnected-(U1F-PE12-Pad43)") (class "Default")
      (node (ref "U1") (pin "43") (pinfunction "PE12_43") (pintype "bidirectional"))
    )
    (net (code "113") (name "unconnected-(U1F-PE13-Pad44)") (class "Default")
      (node (ref "U1") (pin "44") (pinfunction "PE13_44") (pintype "bidirectional"))
    )
    (net (code "114") (name "unconnected-(U1F-PE14-Pad45)") (class "Default")
      (node (ref "U1") (pin "45") (pinfunction "PE14_45") (pintype "bidirectional"))
    )
    (net (code "115") (name "unconnected-(U1F-PE15-Pad46)") (class "Default")
      (node (ref "U1") (pin "46") (pinfunction "PE15_46") (pintype "bidirectional"))
    )
    (net (code "116") (name "unconnected-(U1G-PD4-Pad85)") (class "Default")
      (node (ref "U1") (pin "85") (pinfunction "PD4_85") (pintype "bidirectional"))
    )
    (net (code "117") (name "unconnected-(U1G-PD6-Pad87)") (class "Default")
      (node (ref "U1") (pin "87") (pinfunction "PD6_87") (pintype "bidirectional+no_connect"))
    )
    (net (code "118") (name "unconnected-(U1G-PD7-Pad88)") (class "Default")
      (node (ref "U1") (pin "88") (pinfunction "PD7_88") (pintype "bidirectional+no_connect"))
    )
    (net (code "119") (name "unconnected-(U1G-PD12-Pad59)") (class "Default")
      (node (ref "U1") (pin "59") (pinfunction "PD12_59") (pintype "bidirectional"))
    )
    (net (code "120") (name "unconnected-(U1G-PD13-Pad60)") (class "Default")
      (node (ref "U1") (pin "60") (pinfunction "PD13_60") (pintype "bidirectional"))
    )
    (net (code "121") (name "unconnected-(U4-COMP-Pad5)") (class "Default")
      (node (ref "U4") (pin "5") (pinfunction "COMP_5") (pintype "power_in"))
    )
    (net (code "122") (name "unconnected-(U4-SS-Pad3)") (class "Default")
      (node (ref "U4") (pin "3") (pinfunction "SS_3") (pintype "power_in"))
    )
  )
)
